# RH019_1.net
KiCad netlist of a schematic drawn in EAGLE
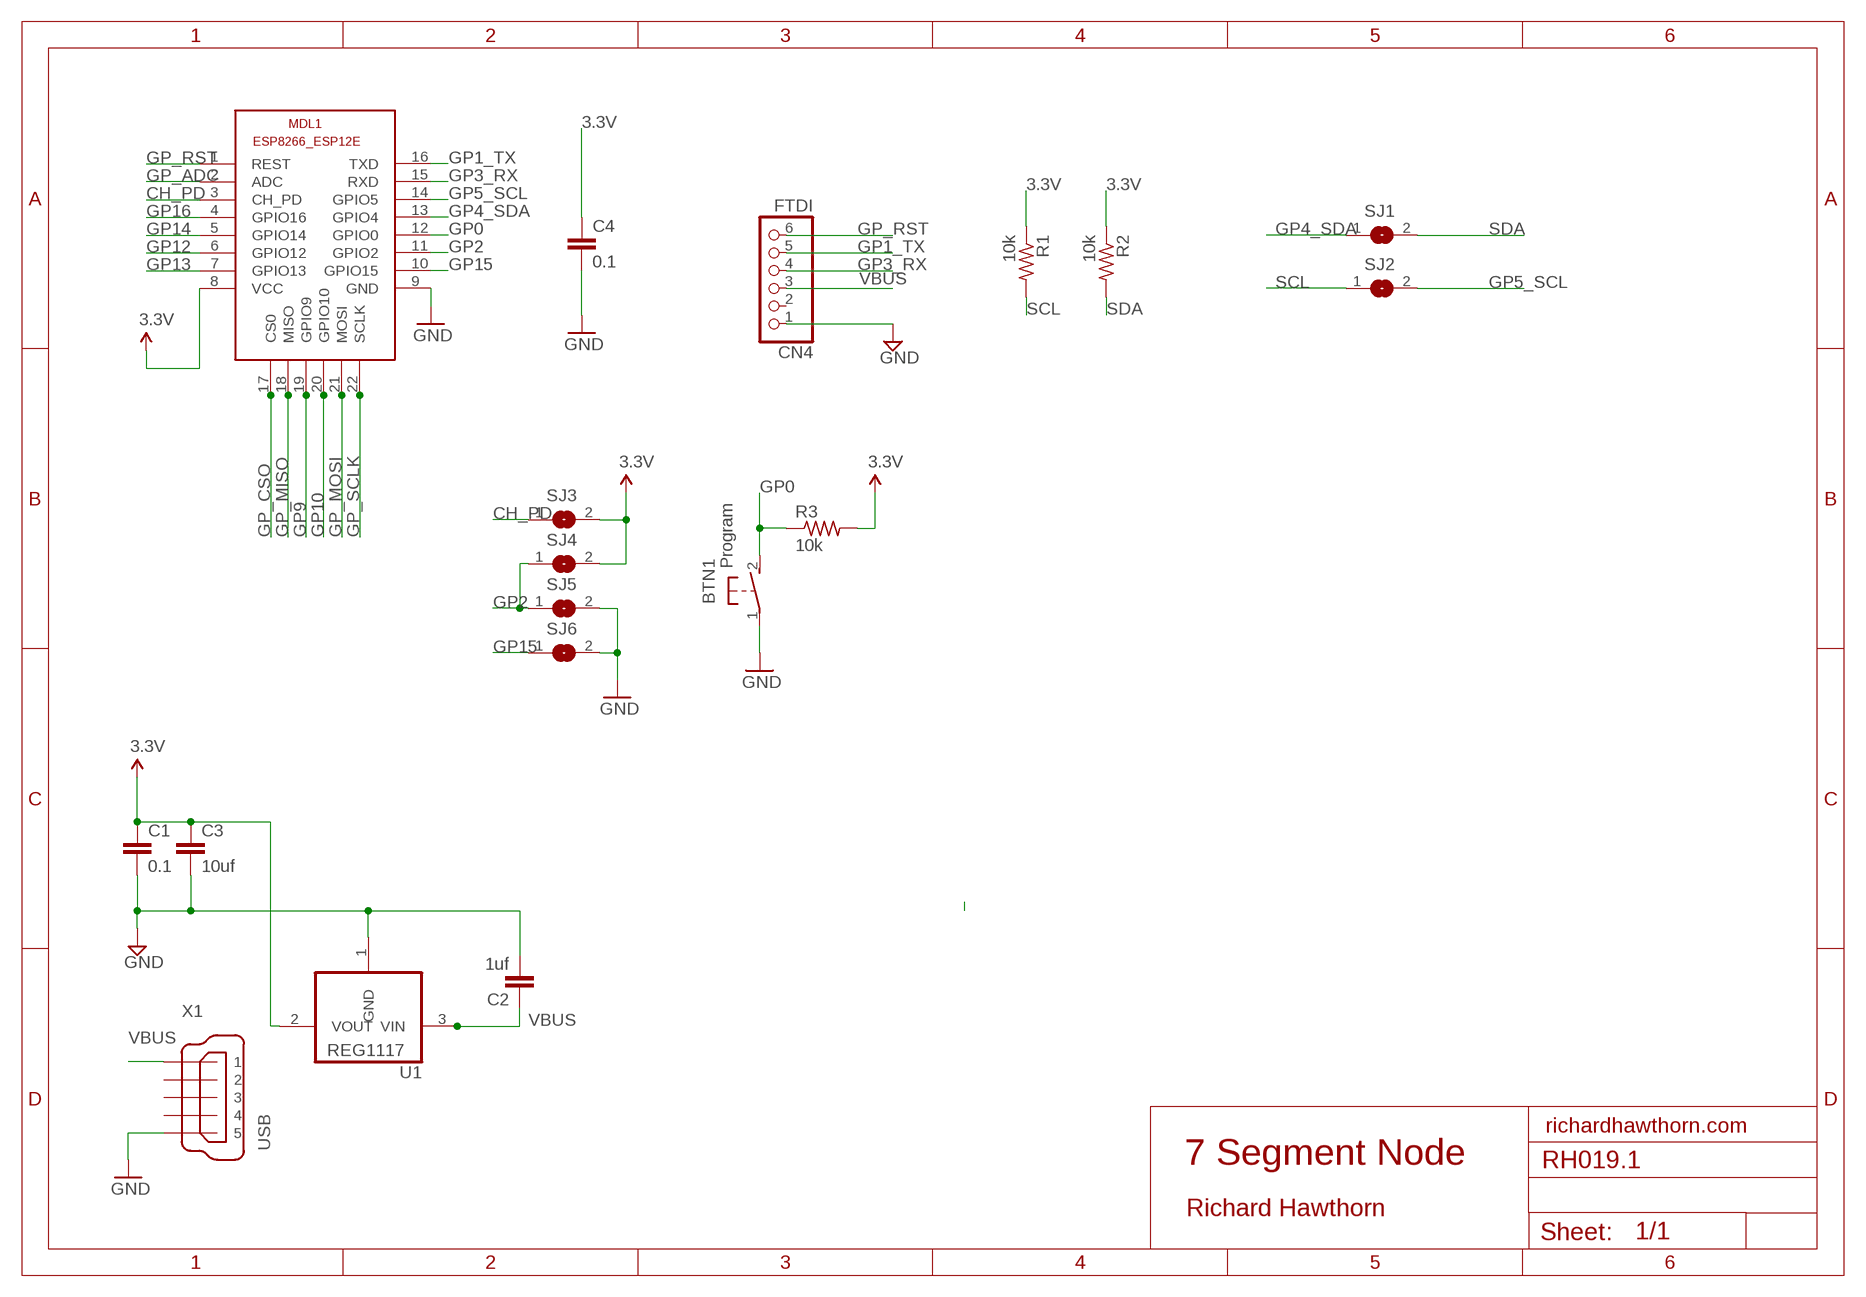
[diagram p0: schematic, sheet 1, part 1 of 2]
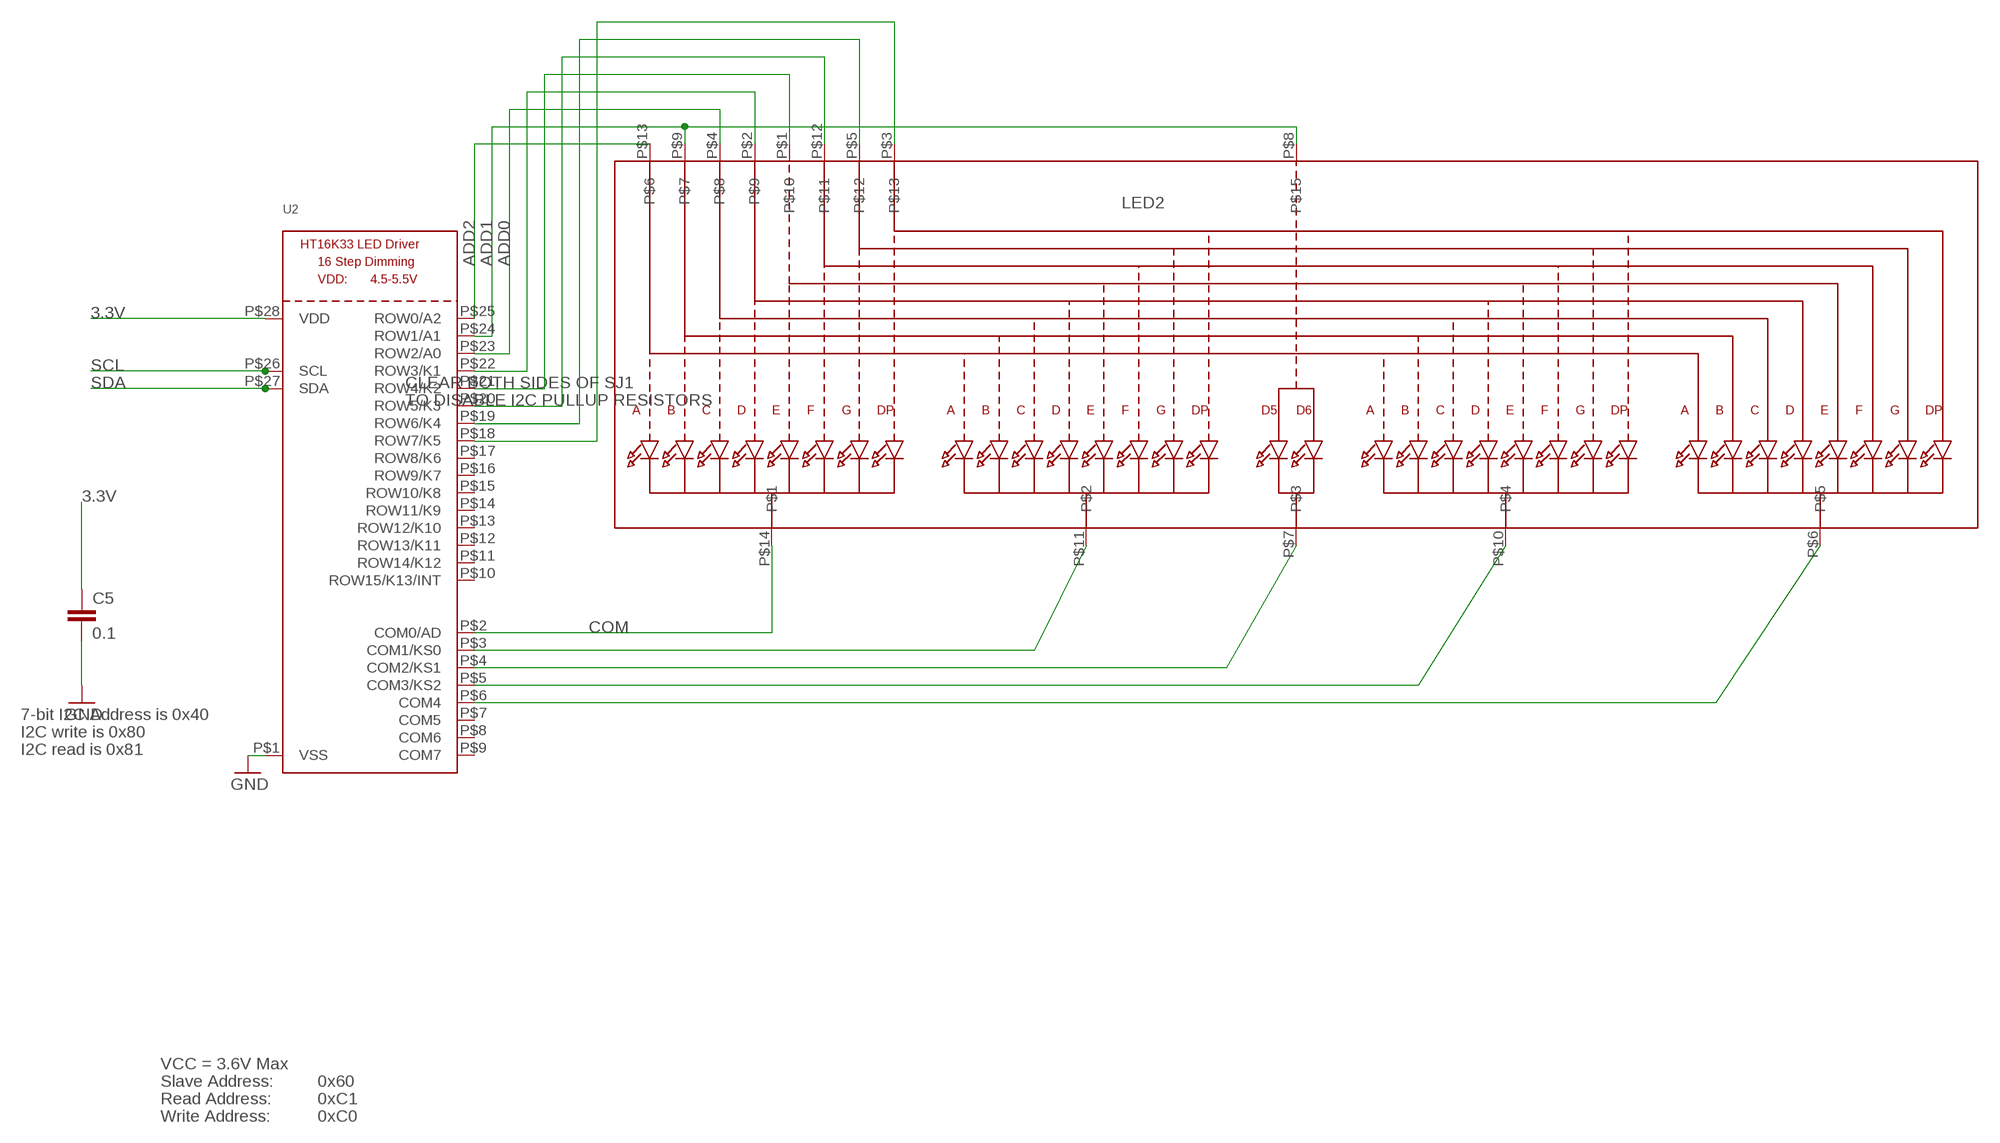
[diagram p1: schematic, sheet 1, part 2 of 2]

(export (version "E")
  (design (tool "Eeschema 10.0.6"))
  (components
    (comp (ref "BTN1")
      (value "Program")
      (footprint "eagle-import:DTS-3")
      (libsource (lib "eagle-import") (part "DTS-3"))
    )
    (comp (ref "C1")
      (value "0.1")
      (footprint "eagle-import:CAP-PTH-SMALL2")
      (libsource (lib "eagle-import") (part "CAPPTH2"))
    )
    (comp (ref "C2")
      (value "1uf")
      (footprint "eagle-import:CAP-PTH-SMALL2")
      (libsource (lib "eagle-import") (part "CAPPTH2"))
    )
    (comp (ref "C3")
      (value "10uf")
      (footprint "eagle-import:CAP-PTH-SMALL2")
      (libsource (lib "eagle-import") (part "CAPPTH2"))
    )
    (comp (ref "C4")
      (value "0.1")
      (footprint "eagle-import:CAP-PTH-SMALL2")
      (libsource (lib "eagle-import") (part "CAPPTH2"))
    )
    (comp (ref "C5")
      (value "0.1")
      (footprint "eagle-import:CAP-PTH-SMALL2")
      (libsource (lib "eagle-import") (part "CAPPTH2"))
    )
    (comp (ref "CN4")
      (value "FTDI")
      (footprint "eagle-import:1X06")
      (libsource (lib "eagle-import") (part "PINHD-1X6"))
    )
    (comp (ref "LED2")
      (value "DISP_SEGMENT_4DIGIT_BL-Q56C43")
      (footprint "eagle-import:SEGMENT-BL-Q56C43")
      (libsource (lib "eagle-import") (part "DISP_SEGMENT_4DIGIT_BL-Q56C43"))
    )
    (comp (ref "MDL1")
      (value "ESP8266-12EESP8266-ESP12E")
      (footprint "eagle-import:ESP8266-ESP12E")
      (libsource (lib "eagle-import") (part "ESP8266-12EESP8266-ESP12E"))
    )
    (comp (ref "R1")
      (value "10k")
      (footprint "eagle-import:0204_7")
      (libsource (lib "eagle-import") (part "R-US_0204/7"))
    )
    (comp (ref "R2")
      (value "10k")
      (footprint "eagle-import:0204_7")
      (libsource (lib "eagle-import") (part "R-US_0204/7"))
    )
    (comp (ref "R3")
      (value "10k")
      (footprint "eagle-import:0204_7")
      (libsource (lib "eagle-import") (part "R-US_0204/7"))
    )
    (comp (ref "SJ1") (value "SJ") (footprint "eagle-import:SJ") (libsource (lib "eagle-import") (part "SJ")))
    (comp (ref "SJ2") (value "SJ") (footprint "eagle-import:SJ") (libsource (lib "eagle-import") (part "SJ")))
    (comp (ref "SJ3") (value "SJ") (footprint "eagle-import:SJ") (libsource (lib "eagle-import") (part "SJ")))
    (comp (ref "SJ4") (value "SJ") (footprint "eagle-import:SJ") (libsource (lib "eagle-import") (part "SJ")))
    (comp (ref "SJ5") (value "SJ") (footprint "eagle-import:SJ") (libsource (lib "eagle-import") (part "SJ")))
    (comp (ref "SJ6") (value "SJ") (footprint "eagle-import:SJ") (libsource (lib "eagle-import") (part "SJ")))
    (comp (ref "U1")
      (value "REG1117")
      (footprint "eagle-import:SOT223")
      (libsource (lib "eagle-import") (part "REG1117"))
    )
    (comp (ref "U2")
      (value "HT16K33_SOP28")
      (footprint "eagle-import:SOP28_300MIL")
      (libsource (lib "eagle-import") (part "HT16K33_SOP28"))
    )
    (comp (ref "X1")
      (value "USB")
      (footprint "eagle-import:32005-601")
      (libsource (lib "eagle-import") (part "MINI-USB_SHIELD5P2-32005-601"))
    )
  )
  (nets
    (net (code "1") (name "/ADD0") (class "Default")
      (node (ref "LED2") (pin "P$4") (pinfunction "P$8_P$4") (pintype "bidirectional"))
      (node (ref "U2") (pin "P$23") (pinfunction "ROW2/A0_P$23") (pintype "bidirectional"))
    )
    (net (code "2") (name "/ADD1") (class "Default")
      (node (ref "LED2") (pin "P$8") (pinfunction "P$15_P$8") (pintype "bidirectional"))
      (node (ref "LED2") (pin "P$9") (pinfunction "P$7_P$9") (pintype "bidirectional"))
      (node (ref "U2") (pin "P$24") (pinfunction "ROW1/A1_P$24") (pintype "bidirectional"))
    )
    (net (code "3") (name "/ADD2") (class "Default")
      (node (ref "LED2") (pin "P$13") (pinfunction "P$6_P$13") (pintype "bidirectional"))
      (node (ref "U2") (pin "P$25") (pinfunction "ROW0/A2_P$25") (pintype "bidirectional"))
    )
    (net (code "4") (name "/CH_PD") (class "Default")
      (node (ref "MDL1") (pin "3") (pinfunction "CH_PD_3") (pintype "bidirectional"))
      (node (ref "SJ3") (pin "1") (pinfunction "1_1") (pintype "passive"))
    )
    (net (code "5") (name "/COM") (class "Default")
      (node (ref "LED2") (pin "P$14") (pinfunction "P$1_P$14") (pintype "bidirectional"))
      (node (ref "U2") (pin "P$2") (pinfunction "COM0/AD_P$2") (pintype "bidirectional"))
    )
    (net (code "6") (name "/GP0") (class "Default")
      (node (ref "BTN1") (pin "2") (pinfunction "2_2") (pintype "passive"))
      (node (ref "MDL1") (pin "12") (pinfunction "GPIO0_12") (pintype "bidirectional"))
      (node (ref "R3") (pin "1") (pinfunction "1_1") (pintype "passive"))
    )
    (net (code "7") (name "/GP1_TX") (class "Default")
      (node (ref "CN4") (pin "5") (pinfunction "5_5") (pintype "passive"))
      (node (ref "MDL1") (pin "16") (pinfunction "TXD_16") (pintype "bidirectional"))
    )
    (net (code "8") (name "/GP2") (class "Default")
      (node (ref "MDL1") (pin "11") (pinfunction "GPIO2_11") (pintype "bidirectional"))
      (node (ref "SJ4") (pin "1") (pinfunction "1_1") (pintype "passive"))
      (node (ref "SJ5") (pin "1") (pinfunction "1_1") (pintype "passive"))
    )
    (net (code "9") (name "/GP3_RX") (class "Default")
      (node (ref "CN4") (pin "4") (pinfunction "4_4") (pintype "passive"))
      (node (ref "MDL1") (pin "15") (pinfunction "RXD_15") (pintype "bidirectional"))
    )
    (net (code "10") (name "/GP4_SDA") (class "Default")
      (node (ref "MDL1") (pin "13") (pinfunction "GPIO4_13") (pintype "bidirectional"))
      (node (ref "SJ1") (pin "1") (pinfunction "1_1") (pintype "passive"))
    )
    (net (code "11") (name "/GP5_SCL") (class "Default")
      (node (ref "MDL1") (pin "14") (pinfunction "GPIO5_14") (pintype "bidirectional"))
      (node (ref "SJ2") (pin "2") (pinfunction "2_2") (pintype "passive"))
    )
    (net (code "12") (name "/GP9") (class "Default")
      (node (ref "MDL1") (pin "19") (pinfunction "GPIO9_19") (pintype "bidirectional"))
    )
    (net (code "13") (name "/GP10") (class "Default")
      (node (ref "MDL1") (pin "20") (pinfunction "GPIO10_20") (pintype "bidirectional"))
    )
    (net (code "14") (name "/GP12") (class "Default")
      (node (ref "MDL1") (pin "6") (pinfunction "GPIO12_6") (pintype "bidirectional"))
    )
    (net (code "15") (name "/GP13") (class "Default")
      (node (ref "MDL1") (pin "7") (pinfunction "GPIO13_7") (pintype "bidirectional"))
    )
    (net (code "16") (name "/GP14") (class "Default")
      (node (ref "MDL1") (pin "5") (pinfunction "GPIO14_5") (pintype "bidirectional"))
    )
    (net (code "17") (name "/GP15") (class "Default")
      (node (ref "MDL1") (pin "10") (pinfunction "GPIO15_10") (pintype "bidirectional"))
      (node (ref "SJ6") (pin "1") (pinfunction "1_1") (pintype "passive"))
    )
    (net (code "18") (name "/GP16") (class "Default")
      (node (ref "MDL1") (pin "4") (pinfunction "GPIO16_4") (pintype "bidirectional"))
    )
    (net (code "19") (name "/GP_ADC") (class "Default")
      (node (ref "MDL1") (pin "2") (pinfunction "ADC_2") (pintype "bidirectional"))
    )
    (net (code "20") (name "/GP_CSO") (class "Default")
      (node (ref "MDL1") (pin "17") (pinfunction "CS0_17") (pintype "bidirectional"))
    )
    (net (code "21") (name "/GP_MISO") (class "Default")
      (node (ref "MDL1") (pin "18") (pinfunction "MISO_18") (pintype "bidirectional"))
    )
    (net (code "22") (name "/GP_MOSI") (class "Default")
      (node (ref "MDL1") (pin "21") (pinfunction "MOSI_21") (pintype "bidirectional"))
    )
    (net (code "23") (name "/GP_RST") (class "Default")
      (node (ref "CN4") (pin "6") (pinfunction "6_6") (pintype "passive"))
      (node (ref "MDL1") (pin "1") (pinfunction "REST_1") (pintype "bidirectional"))
    )
    (net (code "24") (name "/GP_SCLK") (class "Default")
      (node (ref "MDL1") (pin "22") (pinfunction "SCLK_22") (pintype "bidirectional"))
    )
    (net (code "25") (name "/SCL") (class "Default")
      (node (ref "R1") (pin "2") (pinfunction "2_2") (pintype "passive"))
      (node (ref "SJ2") (pin "1") (pinfunction "1_1") (pintype "passive"))
      (node (ref "U2") (pin "P$26") (pinfunction "SCL_P$26") (pintype "bidirectional"))
    )
    (net (code "26") (name "/SDA") (class "Default")
      (node (ref "R2") (pin "2") (pinfunction "2_2") (pintype "passive"))
      (node (ref "SJ1") (pin "2") (pinfunction "2_2") (pintype "passive"))
      (node (ref "U2") (pin "P$27") (pinfunction "SDA_P$27") (pintype "bidirectional"))
    )
    (net (code "27") (name "/VBUS") (class "Default")
      (node (ref "C2") (pin "1") (pinfunction "1_1") (pintype "passive"))
      (node (ref "CN4") (pin "3") (pinfunction "3_3") (pintype "passive"))
      (node (ref "U1") (pin "3") (pinfunction "VIN_3") (pintype "input"))
      (node (ref "X1") (pin "1") (pinfunction "1_1") (pintype "passive"))
    )
    (net (code "28") (name "3.3V") (class "Default")
      (node (ref "C1") (pin "1") (pinfunction "1_1") (pintype "passive"))
      (node (ref "C3") (pin "1") (pinfunction "1_1") (pintype "passive"))
      (node (ref "C4") (pin "1") (pinfunction "1_1") (pintype "passive"))
      (node (ref "C5") (pin "1") (pinfunction "1_1") (pintype "passive"))
      (node (ref "MDL1") (pin "8") (pinfunction "VCC_8") (pintype "bidirectional"))
      (node (ref "R1") (pin "1") (pinfunction "1_1") (pintype "passive"))
      (node (ref "R2") (pin "1") (pinfunction "1_1") (pintype "passive"))
      (node (ref "R3") (pin "2") (pinfunction "2_2") (pintype "passive"))
      (node (ref "SJ3") (pin "2") (pinfunction "2_2") (pintype "passive"))
      (node (ref "SJ4") (pin "2") (pinfunction "2_2") (pintype "passive"))
      (node (ref "U1") (pin "2") (pinfunction "VOUT_2") (pintype "output"))
      (node (ref "U2") (pin "P$28") (pinfunction "VDD_P$28") (pintype "bidirectional"))
    )
    (net (code "29") (name "GND") (class "Default")
      (node (ref "BTN1") (pin "1") (pinfunction "1_1") (pintype "passive"))
      (node (ref "C1") (pin "2") (pinfunction "2_2") (pintype "passive"))
      (node (ref "C2") (pin "2") (pinfunction "2_2") (pintype "passive"))
      (node (ref "C3") (pin "2") (pinfunction "2_2") (pintype "passive"))
      (node (ref "C4") (pin "2") (pinfunction "2_2") (pintype "passive"))
      (node (ref "C5") (pin "2") (pinfunction "2_2") (pintype "passive"))
      (node (ref "CN4") (pin "1") (pinfunction "1_1") (pintype "passive"))
      (node (ref "MDL1") (pin "9") (pinfunction "GND_9") (pintype "bidirectional"))
      (node (ref "SJ5") (pin "2") (pinfunction "2_2") (pintype "passive"))
      (node (ref "SJ6") (pin "2") (pinfunction "2_2") (pintype "passive"))
      (node (ref "U1") (pin "1") (pinfunction "GND_1") (pintype "power_in"))
      (node (ref "U2") (pin "P$1") (pinfunction "VSS_P$1") (pintype "bidirectional"))
      (node (ref "X1") (pin "5") (pinfunction "5_5") (pintype "passive"))
    )
    (net (code "30") (name "Net-(LED2-P$2)") (class "Default")
      (node (ref "LED2") (pin "P$11") (pinfunction "P$2_P$11") (pintype "bidirectional"))
      (node (ref "U2") (pin "P$3") (pinfunction "COM1/KS0_P$3") (pintype "bidirectional"))
    )
    (net (code "31") (name "Net-(LED2-P$3)") (class "Default")
      (node (ref "LED2") (pin "P$7") (pinfunction "P$3_P$7") (pintype "bidirectional"))
      (node (ref "U2") (pin "P$4") (pinfunction "COM2/KS1_P$4") (pintype "bidirectional"))
    )
    (net (code "32") (name "Net-(LED2-P$4)") (class "Default")
      (node (ref "LED2") (pin "P$10") (pinfunction "P$4_P$10") (pintype "bidirectional"))
      (node (ref "U2") (pin "P$5") (pinfunction "COM3/KS2_P$5") (pintype "bidirectional"))
    )
    (net (code "33") (name "Net-(LED2-P$5)") (class "Default")
      (node (ref "LED2") (pin "P$6") (pinfunction "P$5_P$6") (pintype "bidirectional"))
      (node (ref "U2") (pin "P$6") (pinfunction "COM4_P$6") (pintype "bidirectional"))
    )
    (net (code "34") (name "Net-(LED2-P$9)") (class "Default")
      (node (ref "LED2") (pin "P$2") (pinfunction "P$9_P$2") (pintype "bidirectional"))
      (node (ref "U2") (pin "P$22") (pinfunction "ROW3/K1_P$22") (pintype "bidirectional"))
    )
    (net (code "35") (name "Net-(LED2-P$10)") (class "Default")
      (node (ref "LED2") (pin "P$1") (pinfunction "P$10_P$1") (pintype "bidirectional"))
      (node (ref "U2") (pin "P$21") (pinfunction "ROW4/K2_P$21") (pintype "bidirectional"))
    )
    (net (code "36") (name "Net-(LED2-P$11)") (class "Default")
      (node (ref "LED2") (pin "P$12") (pinfunction "P$11_P$12") (pintype "bidirectional"))
      (node (ref "U2") (pin "P$20") (pinfunction "ROW5/K3_P$20") (pintype "bidirectional"))
    )
    (net (code "37") (name "Net-(LED2-P$12)") (class "Default")
      (node (ref "LED2") (pin "P$5") (pinfunction "P$12_P$5") (pintype "bidirectional"))
      (node (ref "U2") (pin "P$19") (pinfunction "ROW6/K4_P$19") (pintype "bidirectional"))
    )
    (net (code "38") (name "Net-(LED2-P$13)") (class "Default")
      (node (ref "LED2") (pin "P$3") (pinfunction "P$13_P$3") (pintype "bidirectional"))
      (node (ref "U2") (pin "P$18") (pinfunction "ROW7/K5_P$18") (pintype "bidirectional"))
    )
    (net (code "39") (name "unconnected-(CN4-Pad2)") (class "Default")
      (node (ref "CN4") (pin "2") (pinfunction "2_2") (pintype "passive"))
    )
    (net (code "40") (name "unconnected-(U2-COM5-PadP$7)") (class "Default")
      (node (ref "U2") (pin "P$7") (pinfunction "COM5_P$7") (pintype "bidirectional"))
    )
    (net (code "41") (name "unconnected-(U2-COM6-PadP$8)") (class "Default")
      (node (ref "U2") (pin "P$8") (pinfunction "COM6_P$8") (pintype "bidirectional"))
    )
    (net (code "42") (name "unconnected-(U2-COM7-PadP$9)") (class "Default")
      (node (ref "U2") (pin "P$9") (pinfunction "COM7_P$9") (pintype "bidirectional"))
    )
    (net (code "43") (name "unconnected-(U2-ROW8{slash}K6-PadP$17)") (class "Default")
      (node (ref "U2") (pin "P$17") (pinfunction "ROW8/K6_P$17") (pintype "bidirectional"))
    )
    (net (code "44") (name "unconnected-(U2-ROW9{slash}K7-PadP$16)") (class "Default")
      (node (ref "U2") (pin "P$16") (pinfunction "ROW9/K7_P$16") (pintype "bidirectional"))
    )
    (net (code "45") (name "unconnected-(U2-ROW10{slash}K8-PadP$15)") (class "Default")
      (node (ref "U2") (pin "P$15") (pinfunction "ROW10/K8_P$15") (pintype "bidirectional"))
    )
    (net (code "46") (name "unconnected-(U2-ROW11{slash}K9-PadP$14)") (class "Default")
      (node (ref "U2") (pin "P$14") (pinfunction "ROW11/K9_P$14") (pintype "bidirectional"))
    )
    (net (code "47") (name "unconnected-(U2-ROW12{slash}K10-PadP$13)") (class "Default")
      (node (ref "U2") (pin "P$13") (pinfunction "ROW12/K10_P$13") (pintype "bidirectional"))
    )
    (net (code "48") (name "unconnected-(U2-ROW13{slash}K11-PadP$12)") (class "Default")
      (node (ref "U2") (pin "P$12") (pinfunction "ROW13/K11_P$12") (pintype "bidirectional"))
    )
    (net (code "49") (name "unconnected-(U2-ROW14{slash}K12-PadP$11)") (class "Default")
      (node (ref "U2") (pin "P$11") (pinfunction "ROW14/K12_P$11") (pintype "bidirectional"))
    )
    (net (code "50") (name "unconnected-(U2-ROW15{slash}K13{slash}INT-PadP$10)") (class "Default")
      (node (ref "U2") (pin "P$10") (pinfunction "ROW15/K13/INT_P$10") (pintype "bidirectional"))
    )
    (net (code "51") (name "unconnected-(X1-Pad2)") (class "Default")
      (node (ref "X1") (pin "2") (pinfunction "2_2") (pintype "passive"))
    )
    (net (code "52") (name "unconnected-(X1-Pad3)") (class "Default")
      (node (ref "X1") (pin "3") (pinfunction "3_3") (pintype "passive"))
    )
    (net (code "53") (name "unconnected-(X1-Pad4)") (class "Default")
      (node (ref "X1") (pin "4") (pinfunction "4_4") (pintype "passive"))
    )
  )
)
